# DK_GU600E_V10.net
KiCad netlist of a schematic drawn in Altium Designer
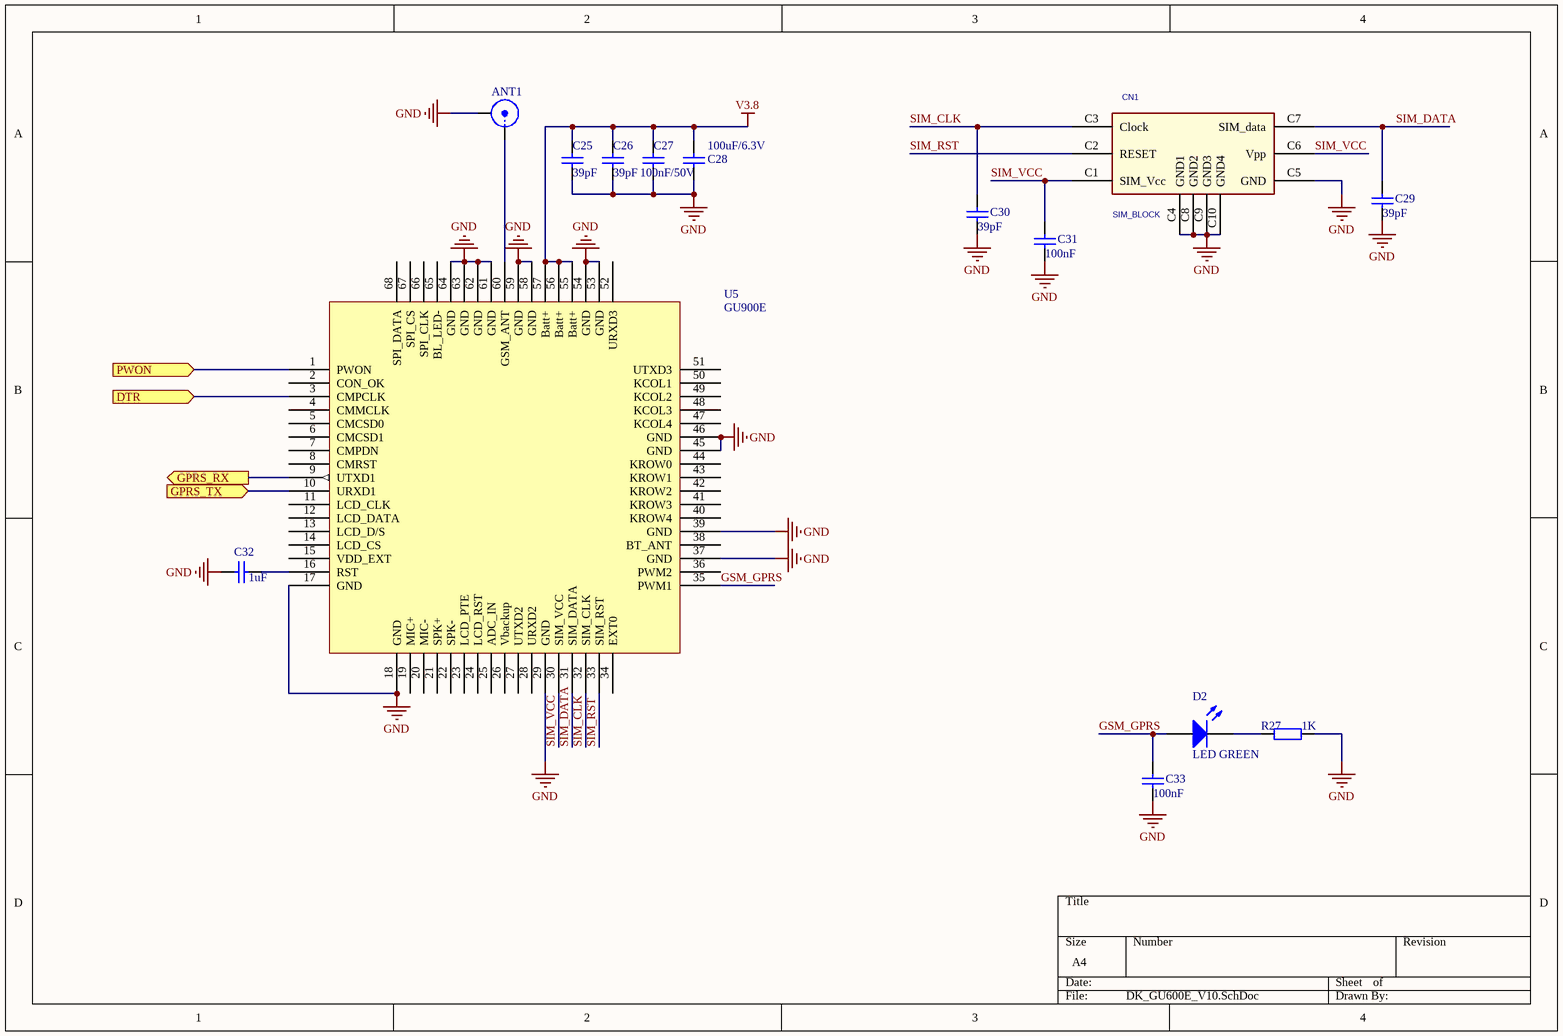
[diagram p0: DK_GU600E_V10.SchDoc]

(export (version "E")
  (design (tool "Eeschema 10.0.6"))
  (components
    (comp (ref "ANT1")
      (value "SMB")
      (footprint "SMB_V-RJ45")
      (description "SMB Straight Connector")
      (fields (field (name "PUBLISHER") "Altium Limited"))
      (libsource (lib "Miscellaneous Connectors") (part "SMB"))
    )
    (comp (ref "C25")
      (value "39pF")
      (footprint "0603")
      (description "Capacitor")
      (fields (field (name "Comment") "Cap") (field (name "PUBLISHER") "Altium Limited"))
      (libsource (lib "Miscellaneous Devices") (part "Cap"))
    )
    (comp (ref "C26")
      (value "39pF")
      (footprint "0603")
      (description "Capacitor")
      (fields (field (name "Comment") "Cap") (field (name "PUBLISHER") "Altium Limited"))
      (libsource (lib "Miscellaneous Devices") (part "Cap"))
    )
    (comp (ref "C27")
      (value "100nF/50V")
      (footprint "0603")
      (description "Capacitor")
      (fields (field (name "Comment") "Cap") (field (name "PUBLISHER") "Altium Limited"))
      (libsource (lib "Miscellaneous Devices") (part "Cap"))
    )
    (comp (ref "C28")
      (value "100uF/6.3V")
      (footprint "1206")
      (description "Capacitor")
      (fields (field (name "Comment") "Cap") (field (name "PUBLISHER") "Altium Limited"))
      (libsource (lib "Miscellaneous Devices") (part "Cap"))
    )
    (comp (ref "C29")
      (value "39pF")
      (footprint "0603")
      (description "Capacitor")
      (fields (field (name "Comment") "Cap") (field (name "PUBLISHER") "Altium Limited"))
      (libsource (lib "Miscellaneous Devices") (part "Cap"))
    )
    (comp (ref "C30")
      (value "39pF")
      (footprint "0603")
      (description "Capacitor")
      (fields (field (name "Comment") "Cap") (field (name "PUBLISHER") "Altium Limited"))
      (libsource (lib "Miscellaneous Devices") (part "Cap"))
    )
    (comp (ref "C31")
      (value "100nF")
      (footprint "0603")
      (description "Capacitor")
      (fields (field (name "Comment") "Cap") (field (name "PUBLISHER") "Altium Limited"))
      (libsource (lib "Miscellaneous Devices") (part "Cap"))
    )
    (comp (ref "C32")
      (value "1uF")
      (footprint "0603")
      (description "Capacitor")
      (fields (field (name "Comment") "Cap") (field (name "PUBLISHER") "Altium Limited"))
      (libsource (lib "Miscellaneous Devices") (part "Cap"))
    )
    (comp (ref "C33")
      (value "100nF")
      (footprint "0603")
      (description "Capacitor")
      (fields (field (name "Comment") "Cap") (field (name "PUBLISHER") "Altium Limited"))
      (libsource (lib "Miscellaneous Devices") (part "Cap"))
    )
    (comp (ref "CN1")
      (value "SIM_BLOCK")
      (footprint "SIM_BLOCK")
      (libsource (lib "TB906") (part "SIM_BLOCK_2"))
    )
    (comp (ref "D2")
      (value "LED GREEN")
      (footprint "LED0603")
      (description "Typical RED, GREEN, YELLOW, AMBER GaAs LED")
      (fields (field (name "PUBLISHER") "Altium Limited"))
      (libsource (lib "Miscellaneous Devices") (part "LED2"))
    )
    (comp (ref "R27")
      (value "1K")
      (footprint "0603")
      (description "Resistor")
      (fields (field (name "Comment") "Res2") (field (name "PUBLISHER") "Altium Limited"))
      (libsource (lib "Miscellaneous Devices") (part "Res2"))
    )
    (comp (ref "U5") (value "GU900E") (footprint "SIM900-68P") (libsource (lib "GU900E") (part "GU900E")))
  )
  (nets
    (net (code "1") (name "/DTR") (class "Default")
      (node (ref "U5") (pin "3") (pinfunction "CMPCLK_3") (pintype "passive"))
    )
    (net (code "2") (name "/GPRS_RX") (class "Default")
      (node (ref "U5") (pin "9") (pinfunction "UTXD1_9") (pintype "output"))
    )
    (net (code "3") (name "/GPRS_TX") (class "Default")
      (node (ref "U5") (pin "10") (pinfunction "URXD1_10") (pintype "passive"))
    )
    (net (code "4") (name "/GSM_GPRS") (class "Default")
      (node (ref "C33") (pin "2") (pinfunction "2_2") (pintype "passive"))
      (node (ref "D2") (pin "1") (pinfunction "A_1") (pintype "passive"))
      (node (ref "U5") (pin "35") (pinfunction "PWM1_35") (pintype "passive"))
    )
    (net (code "5") (name "/PWON") (class "Default")
      (node (ref "U5") (pin "1") (pinfunction "PWON_1") (pintype "passive"))
    )
    (net (code "6") (name "/SIM_CLK") (class "Default")
      (node (ref "C30") (pin "2") (pinfunction "2_2") (pintype "passive"))
      (node (ref "CN1") (pin "C3") (pinfunction "Clock_C3") (pintype "passive"))
      (node (ref "U5") (pin "32") (pinfunction "SIM_CLK_32") (pintype "passive"))
    )
    (net (code "7") (name "/SIM_DATA") (class "Default")
      (node (ref "C29") (pin "2") (pinfunction "2_2") (pintype "passive"))
      (node (ref "CN1") (pin "C7") (pinfunction "SIM_data_C7") (pintype "passive"))
      (node (ref "U5") (pin "31") (pinfunction "SIM_DATA_31") (pintype "passive"))
    )
    (net (code "8") (name "/SIM_RST") (class "Default")
      (node (ref "CN1") (pin "C2") (pinfunction "RESET_C2") (pintype "passive"))
      (node (ref "U5") (pin "33") (pinfunction "SIM_RST_33") (pintype "passive"))
    )
    (net (code "9") (name "/SIM_VCC") (class "Default")
      (node (ref "C31") (pin "2") (pinfunction "2_2") (pintype "passive"))
      (node (ref "CN1") (pin "C1") (pinfunction "SIM_Vcc_C1") (pintype "passive"))
      (node (ref "CN1") (pin "C6") (pinfunction "Vpp_C6") (pintype "passive"))
      (node (ref "U5") (pin "30") (pinfunction "SIM_VCC_30") (pintype "passive"))
    )
    (net (code "10") (name "GND") (class "Default")
      (node (ref "ANT1") (pin "2") (pinfunction "Y_2") (pintype "passive"))
      (node (ref "C25") (pin "1") (pinfunction "1_1") (pintype "passive"))
      (node (ref "C26") (pin "1") (pinfunction "1_1") (pintype "passive"))
      (node (ref "C27") (pin "1") (pinfunction "1_1") (pintype "passive"))
      (node (ref "C28") (pin "1") (pinfunction "1_1") (pintype "passive"))
      (node (ref "C29") (pin "1") (pinfunction "1_1") (pintype "passive"))
      (node (ref "C30") (pin "1") (pinfunction "1_1") (pintype "passive"))
      (node (ref "C31") (pin "1") (pinfunction "1_1") (pintype "passive"))
      (node (ref "C32") (pin "1") (pinfunction "1_1") (pintype "passive"))
      (node (ref "C33") (pin "1") (pinfunction "1_1") (pintype "passive"))
      (node (ref "CN1") (pin "C10") (pinfunction "GND4_C10") (pintype "passive"))
      (node (ref "CN1") (pin "C4") (pinfunction "GND1_C4") (pintype "passive"))
      (node (ref "CN1") (pin "C5") (pinfunction "GND_C5") (pintype "passive"))
      (node (ref "CN1") (pin "C8") (pinfunction "GND2_C8") (pintype "passive"))
      (node (ref "CN1") (pin "C9") (pinfunction "GND3_C9") (pintype "passive"))
      (node (ref "R27") (pin "2") (pinfunction "2_2") (pintype "passive"))
      (node (ref "U5") (pin "17") (pinfunction "GND_17") (pintype "passive"))
      (node (ref "U5") (pin "18") (pinfunction "GND_18") (pintype "passive"))
      (node (ref "U5") (pin "29") (pinfunction "GND_29") (pintype "passive"))
      (node (ref "U5") (pin "37") (pinfunction "GND_37") (pintype "passive"))
      (node (ref "U5") (pin "39") (pinfunction "GND_39") (pintype "passive"))
      (node (ref "U5") (pin "45") (pinfunction "GND_45") (pintype "passive"))
      (node (ref "U5") (pin "46") (pinfunction "GND_46") (pintype "passive"))
      (node (ref "U5") (pin "53") (pinfunction "GND_53") (pintype "passive"))
      (node (ref "U5") (pin "54") (pinfunction "GND_54") (pintype "passive"))
      (node (ref "U5") (pin "58") (pinfunction "GND_58") (pintype "passive"))
      (node (ref "U5") (pin "59") (pinfunction "GND_59") (pintype "passive"))
      (node (ref "U5") (pin "61") (pinfunction "GND_61") (pintype "passive"))
      (node (ref "U5") (pin "62") (pinfunction "GND_62") (pintype "passive"))
      (node (ref "U5") (pin "63") (pinfunction "GND_63") (pintype "passive"))
      (node (ref "U5") (pin "64") (pinfunction "GND_64") (pintype "passive"))
    )
    (net (code "11") (name "Net-(ANT1-X)") (class "Default")
      (node (ref "ANT1") (pin "1") (pinfunction "X_1") (pintype "passive"))
      (node (ref "U5") (pin "60") (pinfunction "GSM_ANT_60") (pintype "passive"))
    )
    (net (code "12") (name "Net-(D2-K)") (class "Default")
      (node (ref "D2") (pin "2") (pinfunction "K_2") (pintype "passive"))
      (node (ref "R27") (pin "1") (pinfunction "1_1") (pintype "passive"))
    )
    (net (code "13") (name "Net-(U5-RST)") (class "Default")
      (node (ref "C32") (pin "2") (pinfunction "2_2") (pintype "passive"))
      (node (ref "U5") (pin "16") (pinfunction "RST_16") (pintype "passive"))
    )
    (net (code "14") (name "V3.8") (class "Default")
      (node (ref "C25") (pin "2") (pinfunction "2_2") (pintype "passive"))
      (node (ref "C26") (pin "2") (pinfunction "2_2") (pintype "passive"))
      (node (ref "C27") (pin "2") (pinfunction "2_2") (pintype "passive"))
      (node (ref "C28") (pin "2") (pinfunction "2_2") (pintype "passive"))
      (node (ref "U5") (pin "55") (pinfunction "Batt+_55") (pintype "passive"))
      (node (ref "U5") (pin "56") (pinfunction "Batt+_56") (pintype "passive"))
      (node (ref "U5") (pin "57") (pinfunction "Batt+_57") (pintype "passive"))
    )
    (net (code "15") (name "unconnected-(U5-ADC_IN-Pad25)") (class "Default")
      (node (ref "U5") (pin "25") (pinfunction "ADC_IN_25") (pintype "passive"))
    )
    (net (code "16") (name "unconnected-(U5-BL_LED--Pad65)") (class "Default")
      (node (ref "U5") (pin "65") (pinfunction "BL_LED-_65") (pintype "passive"))
    )
    (net (code "17") (name "unconnected-(U5-BT_ANT-Pad38)") (class "Default")
      (node (ref "U5") (pin "38") (pinfunction "BT_ANT_38") (pintype "passive"))
    )
    (net (code "18") (name "unconnected-(U5-CMCSD0-Pad5)") (class "Default")
      (node (ref "U5") (pin "5") (pinfunction "CMCSD0_5") (pintype "passive"))
    )
    (net (code "19") (name "unconnected-(U5-CMCSD1-Pad6)") (class "Default")
      (node (ref "U5") (pin "6") (pinfunction "CMCSD1_6") (pintype "passive"))
    )
    (net (code "20") (name "unconnected-(U5-CMMCLK-Pad4)") (class "Default")
      (node (ref "U5") (pin "4") (pinfunction "CMMCLK_4") (pintype "passive"))
    )
    (net (code "21") (name "unconnected-(U5-CMPDN-Pad7)") (class "Default")
      (node (ref "U5") (pin "7") (pinfunction "CMPDN_7") (pintype "passive"))
    )
    (net (code "22") (name "unconnected-(U5-CMRST-Pad8)") (class "Default")
      (node (ref "U5") (pin "8") (pinfunction "CMRST_8") (pintype "passive"))
    )
    (net (code "23") (name "unconnected-(U5-CON_OK-Pad2)") (class "Default")
      (node (ref "U5") (pin "2") (pinfunction "CON_OK_2") (pintype "passive"))
    )
    (net (code "24") (name "unconnected-(U5-EXT0-Pad34)") (class "Default")
      (node (ref "U5") (pin "34") (pinfunction "EXT0_34") (pintype "passive"))
    )
    (net (code "25") (name "unconnected-(U5-KCOL1-Pad50)") (class "Default")
      (node (ref "U5") (pin "50") (pinfunction "KCOL1_50") (pintype "passive"))
    )
    (net (code "26") (name "unconnected-(U5-KCOL2-Pad49)") (class "Default")
      (node (ref "U5") (pin "49") (pinfunction "KCOL2_49") (pintype "passive"))
    )
    (net (code "27") (name "unconnected-(U5-KCOL3-Pad48)") (class "Default")
      (node (ref "U5") (pin "48") (pinfunction "KCOL3_48") (pintype "passive"))
    )
    (net (code "28") (name "unconnected-(U5-KCOL4-Pad47)") (class "Default")
      (node (ref "U5") (pin "47") (pinfunction "KCOL4_47") (pintype "passive"))
    )
    (net (code "29") (name "unconnected-(U5-KROW0-Pad44)") (class "Default")
      (node (ref "U5") (pin "44") (pinfunction "KROW0_44") (pintype "passive"))
    )
    (net (code "30") (name "unconnected-(U5-KROW1-Pad43)") (class "Default")
      (node (ref "U5") (pin "43") (pinfunction "KROW1_43") (pintype "passive"))
    )
    (net (code "31") (name "unconnected-(U5-KROW2-Pad42)") (class "Default")
      (node (ref "U5") (pin "42") (pinfunction "KROW2_42") (pintype "passive"))
    )
    (net (code "32") (name "unconnected-(U5-KROW3-Pad41)") (class "Default")
      (node (ref "U5") (pin "41") (pinfunction "KROW3_41") (pintype "passive"))
    )
    (net (code "33") (name "unconnected-(U5-KROW4-Pad40)") (class "Default")
      (node (ref "U5") (pin "40") (pinfunction "KROW4_40") (pintype "passive"))
    )
    (net (code "34") (name "unconnected-(U5-LCD_CLK-Pad11)") (class "Default")
      (node (ref "U5") (pin "11") (pinfunction "LCD_CLK_11") (pintype "passive"))
    )
    (net (code "35") (name "unconnected-(U5-LCD_CS-Pad14)") (class "Default")
      (node (ref "U5") (pin "14") (pinfunction "LCD_CS_14") (pintype "passive"))
    )
    (net (code "36") (name "unconnected-(U5-LCD_DATA-Pad12)") (class "Default")
      (node (ref "U5") (pin "12") (pinfunction "LCD_DATA_12") (pintype "passive"))
    )
    (net (code "37") (name "unconnected-(U5-LCD_D{slash}S-Pad13)") (class "Default")
      (node (ref "U5") (pin "13") (pinfunction "LCD_D/S_13") (pintype "passive"))
    )
    (net (code "38") (name "unconnected-(U5-LCD_PTE-Pad23)") (class "Default")
      (node (ref "U5") (pin "23") (pinfunction "LCD_PTE_23") (pintype "passive"))
    )
    (net (code "39") (name "unconnected-(U5-LCD_RST-Pad24)") (class "Default")
      (node (ref "U5") (pin "24") (pinfunction "LCD_RST_24") (pintype "passive"))
    )
    (net (code "40") (name "unconnected-(U5-MIC+-Pad19)") (class "Default")
      (node (ref "U5") (pin "19") (pinfunction "MIC+_19") (pintype "passive"))
    )
    (net (code "41") (name "unconnected-(U5-MIC--Pad20)") (class "Default")
      (node (ref "U5") (pin "20") (pinfunction "MIC-_20") (pintype "passive"))
    )
    (net (code "42") (name "unconnected-(U5-PWM2-Pad36)") (class "Default")
      (node (ref "U5") (pin "36") (pinfunction "PWM2_36") (pintype "passive"))
    )
    (net (code "43") (name "unconnected-(U5-SPI_CLK-Pad66)") (class "Default")
      (node (ref "U5") (pin "66") (pinfunction "SPI_CLK_66") (pintype "passive"))
    )
    (net (code "44") (name "unconnected-(U5-SPI_CS-Pad67)") (class "Default")
      (node (ref "U5") (pin "67") (pinfunction "SPI_CS_67") (pintype "passive"))
    )
    (net (code "45") (name "unconnected-(U5-SPI_DATA-Pad68)") (class "Default")
      (node (ref "U5") (pin "68") (pinfunction "SPI_DATA_68") (pintype "passive"))
    )
    (net (code "46") (name "unconnected-(U5-SPK+-Pad21)") (class "Default")
      (node (ref "U5") (pin "21") (pinfunction "SPK+_21") (pintype "passive"))
    )
    (net (code "47") (name "unconnected-(U5-SPK--Pad22)") (class "Default")
      (node (ref "U5") (pin "22") (pinfunction "SPK-_22") (pintype "passive"))
    )
    (net (code "48") (name "unconnected-(U5-URXD2-Pad28)") (class "Default")
      (node (ref "U5") (pin "28") (pinfunction "URXD2_28") (pintype "passive"))
    )
    (net (code "49") (name "unconnected-(U5-URXD3-Pad52)") (class "Default")
      (node (ref "U5") (pin "52") (pinfunction "URXD3_52") (pintype "passive"))
    )
    (net (code "50") (name "unconnected-(U5-UTXD2-Pad27)") (class "Default")
      (node (ref "U5") (pin "27") (pinfunction "UTXD2_27") (pintype "passive"))
    )
    (net (code "51") (name "unconnected-(U5-UTXD3-Pad51)") (class "Default")
      (node (ref "U5") (pin "51") (pinfunction "UTXD3_51") (pintype "passive"))
    )
    (net (code "52") (name "unconnected-(U5-VDD_EXT-Pad15)") (class "Default")
      (node (ref "U5") (pin "15") (pinfunction "VDD_EXT_15") (pintype "passive"))
    )
    (net (code "53") (name "unconnected-(U5-Vbackup-Pad26)") (class "Default")
      (node (ref "U5") (pin "26") (pinfunction "Vbackup_26") (pintype "passive"))
    )
  )
)
